# SMA-Q2_replacement_board_v2_2.net
KiCad netlist of a schematic drawn in EAGLE
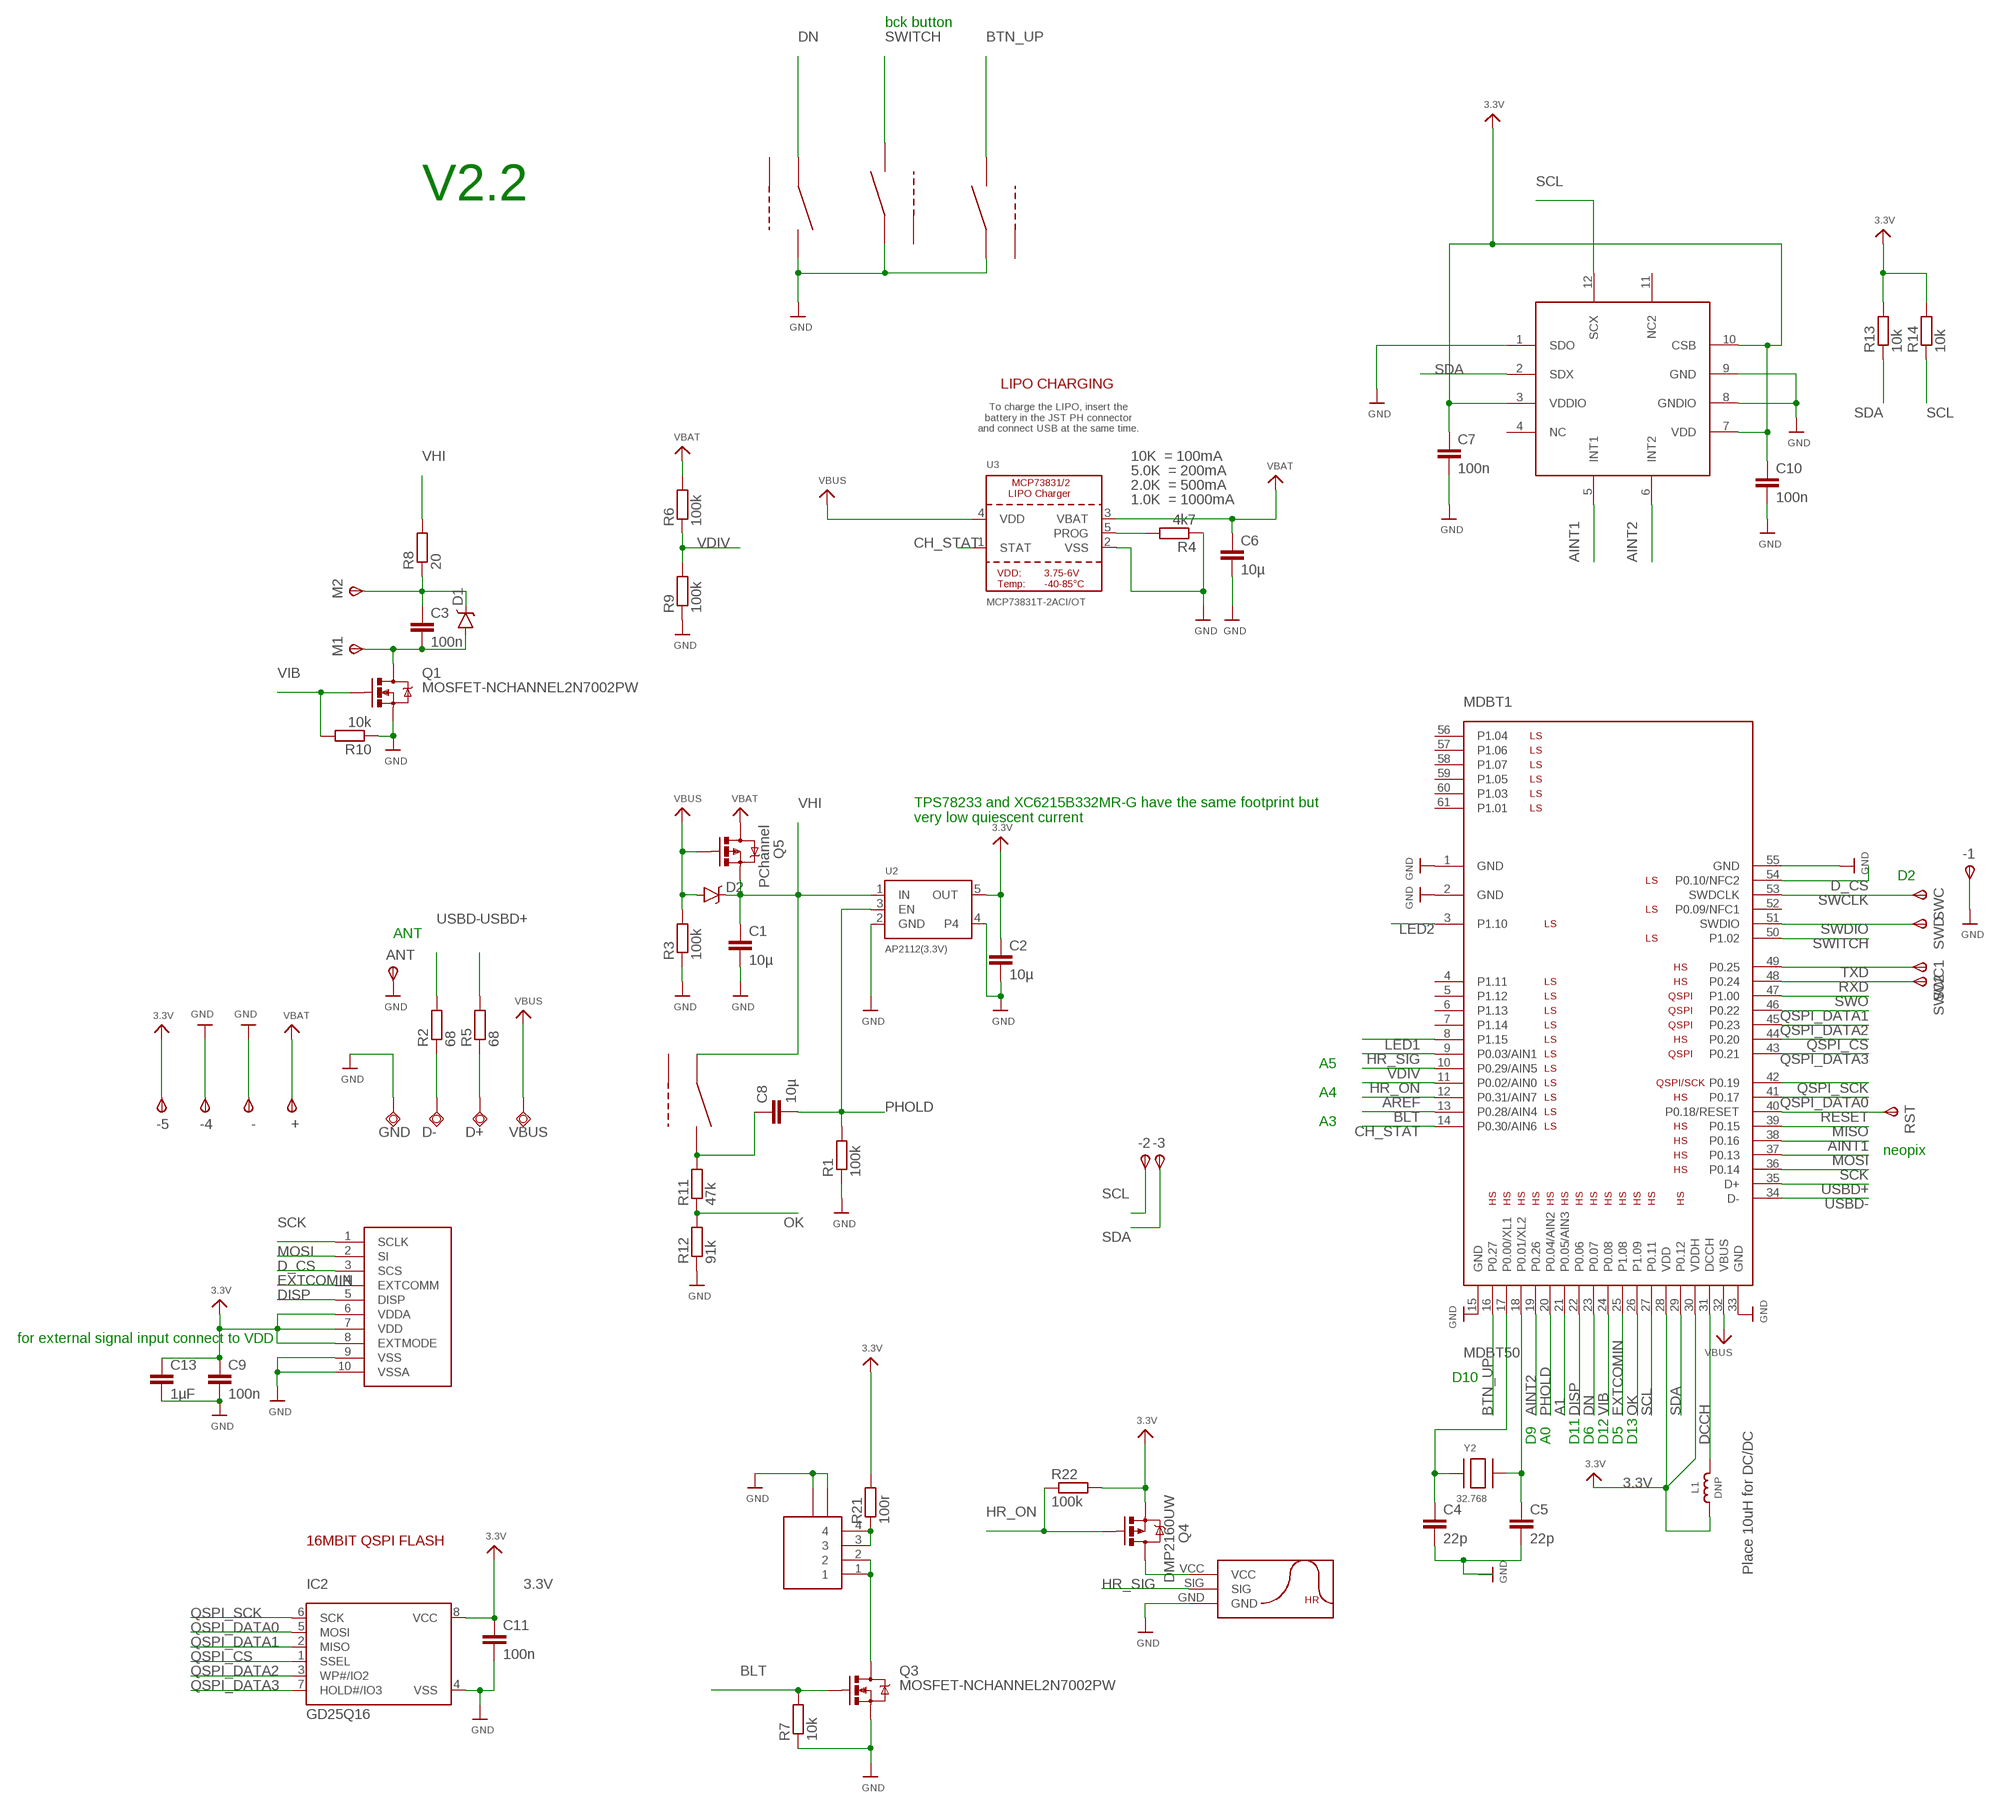
[diagram p0: schematic, sheet 1]

(export (version "E")
  (design (tool "Eeschema 10.0.6"))
  (components
    (comp (ref "+")
      (value "TPSTP09R")
      (footprint "eagle-import:TP09R")
      (libsource (lib "eagle-import") (part "TPSTP09R"))
    )
    (comp (ref "-")
      (value "TPSTP09R")
      (footprint "eagle-import:TP09R")
      (libsource (lib "eagle-import") (part "TPSTP09R"))
    )
    (comp (ref "-1")
      (value "TPSTP09R")
      (footprint "eagle-import:TP09R")
      (libsource (lib "eagle-import") (part "TPSTP09R"))
    )
    (comp (ref "-2")
      (value "TPSTP09R")
      (footprint "eagle-import:TP09R")
      (libsource (lib "eagle-import") (part "TPSTP09R"))
    )
    (comp (ref "-3")
      (value "TPSTP09R")
      (footprint "eagle-import:TP09R")
      (libsource (lib "eagle-import") (part "TPSTP09R"))
    )
    (comp (ref "-4")
      (value "TPSTP09R")
      (footprint "eagle-import:TP09R")
      (libsource (lib "eagle-import") (part "TPSTP09R"))
    )
    (comp (ref "-5")
      (value "TPSTP09R")
      (footprint "eagle-import:TP09R")
      (libsource (lib "eagle-import") (part "TPSTP09R"))
    )
    (comp (ref "ANT")
      (value "TPSTP19SQ")
      (footprint "eagle-import:TP19SQ")
      (libsource (lib "eagle-import") (part "TPSTP19SQ"))
    )
    (comp (ref "C1")
      (value "10µ")
      (footprint "eagle-import:C0603")
      (libsource (lib "eagle-import") (part "C-EUC0603"))
    )
    (comp (ref "C2")
      (value "10µ")
      (footprint "eagle-import:C0603")
      (libsource (lib "eagle-import") (part "C-EUC0603"))
    )
    (comp (ref "C3")
      (value "100n")
      (footprint "eagle-import:C0402")
      (libsource (lib "eagle-import") (part "C-EUC0402"))
    )
    (comp (ref "C4")
      (value "22p")
      (footprint "eagle-import:C0402")
      (libsource (lib "eagle-import") (part "C-EUC0402"))
    )
    (comp (ref "C5")
      (value "22p")
      (footprint "eagle-import:C0402")
      (libsource (lib "eagle-import") (part "C-EUC0402"))
    )
    (comp (ref "C6")
      (value "10µ")
      (footprint "eagle-import:C0603")
      (libsource (lib "eagle-import") (part "C-EUC0603"))
    )
    (comp (ref "C7")
      (value "100n")
      (footprint "eagle-import:C0402")
      (libsource (lib "eagle-import") (part "C-EUC0402"))
    )
    (comp (ref "C8")
      (value "10µ")
      (footprint "eagle-import:C0603")
      (libsource (lib "eagle-import") (part "C-EUC0603"))
    )
    (comp (ref "C9")
      (value "100n")
      (footprint "eagle-import:C0402")
      (libsource (lib "eagle-import") (part "C-EUC0402"))
    )
    (comp (ref "C10")
      (value "100n")
      (footprint "eagle-import:C0402")
      (libsource (lib "eagle-import") (part "C-EUC0402"))
    )
    (comp (ref "C11")
      (value "100n")
      (footprint "eagle-import:C0402")
      (libsource (lib "eagle-import") (part "C-EUC0402"))
    )
    (comp (ref "C13")
      (value "1µF")
      (footprint "eagle-import:C0402")
      (libsource (lib "eagle-import") (part "C-EUC0402"))
    )
    (comp (ref "D+")
      (value "TPSQTP20R")
      (footprint "eagle-import:TP20R")
      (libsource (lib "eagle-import") (part "TPSQTP20R"))
    )
    (comp (ref "D-")
      (value "TPSQTP20R")
      (footprint "eagle-import:TP20R")
      (libsource (lib "eagle-import") (part "TPSQTP20R"))
    )
    (comp (ref "D1")
      (value "BAT20J")
      (footprint "eagle-import:SOD-323")
      (libsource (lib "eagle-import") (part "DIODE-SCHOTTKY-BAT20J"))
    )
    (comp (ref "D2")
      (value "BAT20J")
      (footprint "eagle-import:SOD-323")
      (libsource (lib "eagle-import") (part "DIODE-SCHOTTKY-BAT20J"))
    )
    (comp (ref "DWN")
      (value "LS12T2")
      (footprint "eagle-import:LS12T2")
      (libsource (lib "eagle-import") (part "LS12T2"))
    )
    (comp (ref "DWN1")
      (value "LS12T2")
      (footprint "eagle-import:LS12T2")
      (libsource (lib "eagle-import") (part "LS12T2"))
    )
    (comp (ref "DWN2")
      (value "LS12T2")
      (footprint "eagle-import:LS12T2")
      (libsource (lib "eagle-import") (part "LS12T2"))
    )
    (comp (ref "DWN3")
      (value "LS12T2")
      (footprint "eagle-import:LS12T2")
      (libsource (lib "eagle-import") (part "LS12T2"))
    )
    (comp (ref "GND")
      (value "TPSQTP20R")
      (footprint "eagle-import:TP20R")
      (libsource (lib "eagle-import") (part "TPSQTP20R"))
    )
    (comp (ref "IC2")
      (value "GD25Q16")
      (footprint "eagle-import:USON8")
      (libsource (lib "eagle-import") (part "SPIFLASH_8PINUX"))
    )
    (comp (ref "L1")
      (value "DNP")
      (footprint "eagle-import:_0805MP")
      (libsource (lib "eagle-import") (part "INDUCTOR_0805MP"))
    )
    (comp (ref "M1")
      (value "TPSTP09R")
      (footprint "eagle-import:TP09R")
      (libsource (lib "eagle-import") (part "TPSTP09R"))
    )
    (comp (ref "M2")
      (value "TPSTP09R")
      (footprint "eagle-import:TP09R")
      (libsource (lib "eagle-import") (part "TPSTP09R"))
    )
    (comp (ref "MDBT1")
      (value "MDBT50")
      (footprint "eagle-import:MDBT50")
      (libsource (lib "eagle-import") (part "MDBT50"))
    )
    (comp (ref "Q1")
      (value "MOSFET-NCHANNEL2N7002PW")
      (footprint "eagle-import:SOT323")
      (libsource (lib "eagle-import") (part "MOSFET-NCHANNEL2N7002PW"))
    )
    (comp (ref "Q3")
      (value "MOSFET-NCHANNEL2N7002PW")
      (footprint "eagle-import:SOT323")
      (libsource (lib "eagle-import") (part "MOSFET-NCHANNEL2N7002PW"))
    )
    (comp (ref "Q4")
      (value "DMP2160UW")
      (footprint "eagle-import:SOT323")
      (libsource (lib "eagle-import") (part "MOSFET-P-CHANNEL-DMP2160UW"))
    )
    (comp (ref "Q5")
      (value "PChannel")
      (footprint "eagle-import:SOT323")
      (libsource (lib "eagle-import") (part "MOSFET-P-CHANNEL-DMP2160UW"))
    )
    (comp (ref "R1")
      (value "100k")
      (footprint "eagle-import:R0402")
      (libsource (lib "eagle-import") (part "R-EU_R0402"))
    )
    (comp (ref "R2")
      (value "68")
      (footprint "eagle-import:R0402")
      (libsource (lib "eagle-import") (part "R-EU_R0402"))
    )
    (comp (ref "R3")
      (value "100k")
      (footprint "eagle-import:R0402")
      (libsource (lib "eagle-import") (part "R-EU_R0402"))
    )
    (comp (ref "R4")
      (value "4k7")
      (footprint "eagle-import:R0402")
      (libsource (lib "eagle-import") (part "R-EU_R0402"))
    )
    (comp (ref "R5")
      (value "68")
      (footprint "eagle-import:R0402")
      (libsource (lib "eagle-import") (part "R-EU_R0402"))
    )
    (comp (ref "R6")
      (value "100k")
      (footprint "eagle-import:R0402")
      (libsource (lib "eagle-import") (part "R-EU_R0402"))
    )
    (comp (ref "R7")
      (value "10k")
      (footprint "eagle-import:R0402")
      (libsource (lib "eagle-import") (part "R-EU_R0402"))
    )
    (comp (ref "R8")
      (value "20")
      (footprint "eagle-import:R0402")
      (libsource (lib "eagle-import") (part "R-EU_R0402"))
    )
    (comp (ref "R9")
      (value "100k")
      (footprint "eagle-import:R0402")
      (libsource (lib "eagle-import") (part "R-EU_R0402"))
    )
    (comp (ref "R10")
      (value "10k")
      (footprint "eagle-import:R0402")
      (libsource (lib "eagle-import") (part "R-EU_R0402"))
    )
    (comp (ref "R11")
      (value "47k")
      (footprint "eagle-import:R0402")
      (libsource (lib "eagle-import") (part "R-EU_R0402"))
    )
    (comp (ref "R12")
      (value "91k")
      (footprint "eagle-import:R0402")
      (libsource (lib "eagle-import") (part "R-EU_R0402"))
    )
    (comp (ref "R13")
      (value "10k")
      (footprint "eagle-import:R0402")
      (libsource (lib "eagle-import") (part "R-EU_R0402"))
    )
    (comp (ref "R14")
      (value "10k")
      (footprint "eagle-import:R0402")
      (libsource (lib "eagle-import") (part "R-EU_R0402"))
    )
    (comp (ref "R21")
      (value "100r")
      (footprint "eagle-import:R0402")
      (libsource (lib "eagle-import") (part "R-EU_R0402"))
    )
    (comp (ref "R22")
      (value "100k")
      (footprint "eagle-import:R0402")
      (libsource (lib "eagle-import") (part "R-EU_R0402"))
    )
    (comp (ref "RST")
      (value "TPSTP09R")
      (footprint "eagle-import:TP09R")
      (libsource (lib "eagle-import") (part "TPSTP09R"))
    )
    (comp (ref "SWC")
      (value "TPSTP09R")
      (footprint "eagle-import:TP09R")
      (libsource (lib "eagle-import") (part "TPSTP09R"))
    )
    (comp (ref "SWC1")
      (value "TPSTP09R")
      (footprint "eagle-import:TP09R")
      (libsource (lib "eagle-import") (part "TPSTP09R"))
    )
    (comp (ref "SWC2")
      (value "TPSTP09R")
      (footprint "eagle-import:TP09R")
      (libsource (lib "eagle-import") (part "TPSTP09R"))
    )
    (comp (ref "SWD")
      (value "TPSTP09R")
      (footprint "eagle-import:TP09R")
      (libsource (lib "eagle-import") (part "TPSTP09R"))
    )
    (comp (ref "U$2")
      (value "SHARP_MEM_DISP")
      (footprint "eagle-import:Y5BW")
      (libsource (lib "eagle-import") (part "SHARP_MEM_DISP"))
    )
    (comp (ref "U$6")
      (value "Y5B-4PIN")
      (footprint "eagle-import:Y5B-4PIN")
      (libsource (lib "eagle-import") (part "Y5B-4PIN"))
    )
    (comp (ref "U$7")
      (value "BMA400")
      (footprint "eagle-import:BMA400")
      (libsource (lib "eagle-import") (part "BMA400"))
    )
    (comp (ref "U$45")
      (value "HR_PADS")
      (footprint "eagle-import:HR_PADS")
      (libsource (lib "eagle-import") (part "HR_PADS"))
    )
    (comp (ref "U2")
      (value "AP2112(3.3V)")
      (footprint "eagle-import:SOT23-5")
      (libsource (lib "eagle-import") (part "VREG_SOT23-5"))
    )
    (comp (ref "U3")
      (value "MCP73831T-2ACI/OT")
      (footprint "eagle-import:SOT23-5")
      (libsource (lib "eagle-import") (part "MCP73831/2"))
    )
    (comp (ref "VBUS")
      (value "TPSQTP20R")
      (footprint "eagle-import:TP20R")
      (libsource (lib "eagle-import") (part "TPSQTP20R"))
    )
    (comp (ref "Y2")
      (value "32.768")
      (footprint "eagle-import:XTAL3215")
      (libsource (lib "eagle-import") (part "XTAL-3.2X1.5"))
    )
  )
  (nets
    (net (code "1") (name "/A1") (class "Default")
      (node (ref "MDBT1") (pin "21") (pinfunction "P0.05/AIN3_21") (pintype "bidirectional"))
    )
    (net (code "2") (name "/AINT1") (class "Default")
      (node (ref "MDBT1") (pin "38") (pinfunction "P0.16_38") (pintype "bidirectional"))
      (node (ref "U$7") (pin "5") (pinfunction "INT1_5") (pintype "bidirectional"))
    )
    (net (code "3") (name "/AINT2") (class "Default")
      (node (ref "MDBT1") (pin "19") (pinfunction "P0.26_19") (pintype "bidirectional"))
      (node (ref "U$7") (pin "6") (pinfunction "INT2_6") (pintype "bidirectional"))
    )
    (net (code "4") (name "/AREF") (class "Default")
      (node (ref "MDBT1") (pin "12") (pinfunction "P0.31/AIN7_12") (pintype "bidirectional"))
    )
    (net (code "5") (name "/BLT") (class "Default")
      (node (ref "MDBT1") (pin "13") (pinfunction "P0.28/AIN4_13") (pintype "bidirectional"))
      (node (ref "Q3") (pin "1") (pinfunction "G_1") (pintype "passive"))
      (node (ref "R7") (pin "2") (pinfunction "2_2") (pintype "passive"))
    )
    (net (code "6") (name "/BTN_UP") (class "Default")
      (node (ref "DWN2") (pin "1") (pinfunction "1_1") (pintype "bidirectional"))
      (node (ref "MDBT1") (pin "16") (pinfunction "P0.27_16") (pintype "bidirectional"))
    )
    (net (code "7") (name "/CH_STAT") (class "Default")
      (node (ref "MDBT1") (pin "14") (pinfunction "P0.30/AIN6_14") (pintype "bidirectional"))
      (node (ref "U3") (pin "1") (pinfunction "STAT_1") (pintype "output"))
    )
    (net (code "8") (name "/DCCH") (class "Default")
      (node (ref "L1") (pin "2") (pinfunction "2_2") (pintype "passive"))
      (node (ref "MDBT1") (pin "31") (pinfunction "DCCH_31") (pintype "bidirectional"))
    )
    (net (code "9") (name "/DISP") (class "Default")
      (node (ref "MDBT1") (pin "22") (pinfunction "P0.06_22") (pintype "bidirectional"))
      (node (ref "U$2") (pin "5") (pinfunction "DISP_5") (pintype "bidirectional"))
    )
    (net (code "10") (name "/DN") (class "Default")
      (node (ref "DWN") (pin "2") (pinfunction "2_2") (pintype "bidirectional"))
      (node (ref "MDBT1") (pin "23") (pinfunction "P0.07_23") (pintype "bidirectional"))
    )
    (net (code "11") (name "/D_CS") (class "Default")
      (node (ref "MDBT1") (pin "54") (pinfunction "P0.10/NFC2_54") (pintype "bidirectional"))
      (node (ref "U$2") (pin "3") (pinfunction "SCS_3") (pintype "bidirectional"))
    )
    (net (code "12") (name "/EXTCOMIN") (class "Default")
      (node (ref "MDBT1") (pin "25") (pinfunction "P1.08_25") (pintype "bidirectional"))
      (node (ref "U$2") (pin "4") (pinfunction "EXTCOMM_4") (pintype "bidirectional"))
    )
    (net (code "13") (name "/HR_ON") (class "Default")
      (node (ref "MDBT1") (pin "11") (pinfunction "P0.02/AIN0_11") (pintype "bidirectional"))
      (node (ref "Q4") (pin "1") (pinfunction "G_1") (pintype "passive"))
      (node (ref "R22") (pin "1") (pinfunction "1_1") (pintype "passive"))
    )
    (net (code "14") (name "/HR_SIG") (class "Default")
      (node (ref "MDBT1") (pin "9") (pinfunction "P0.03/AIN1_9") (pintype "bidirectional"))
      (node (ref "U$45") (pin "SIG") (pinfunction "SIG_SIG") (pintype "bidirectional"))
    )
    (net (code "15") (name "/LED1") (class "Default")
      (node (ref "MDBT1") (pin "8") (pinfunction "P1.15_8") (pintype "bidirectional"))
    )
    (net (code "16") (name "/LED2") (class "Default")
      (node (ref "MDBT1") (pin "3") (pinfunction "P1.10_3") (pintype "bidirectional"))
    )
    (net (code "17") (name "/MISO") (class "Default")
      (node (ref "MDBT1") (pin "39") (pinfunction "P0.15_39") (pintype "bidirectional"))
    )
    (net (code "18") (name "/MOSI") (class "Default")
      (node (ref "MDBT1") (pin "37") (pinfunction "P0.13_37") (pintype "bidirectional"))
      (node (ref "U$2") (pin "2") (pinfunction "SI_2") (pintype "bidirectional"))
    )
    (net (code "19") (name "/OK") (class "Default")
      (node (ref "MDBT1") (pin "26") (pinfunction "P1.09_26") (pintype "bidirectional"))
      (node (ref "R11") (pin "1") (pinfunction "1_1") (pintype "passive"))
      (node (ref "R12") (pin "2") (pinfunction "2_2") (pintype "passive"))
    )
    (net (code "20") (name "/PHOLD") (class "Default")
      (node (ref "C8") (pin "2") (pinfunction "2_2") (pintype "passive"))
      (node (ref "MDBT1") (pin "20") (pinfunction "P0.04/AIN2_20") (pintype "bidirectional"))
      (node (ref "R1") (pin "2") (pinfunction "2_2") (pintype "passive"))
      (node (ref "U2") (pin "3") (pinfunction "EN_3") (pintype "input"))
    )
    (net (code "21") (name "/QSPI_CS") (class "Default")
      (node (ref "IC2") (pin "1") (pinfunction "SSEL_1") (pintype "bidirectional"))
      (node (ref "MDBT1") (pin "44") (pinfunction "P0.20_44") (pintype "bidirectional"))
    )
    (net (code "22") (name "/QSPI_DATA0") (class "Default")
      (node (ref "IC2") (pin "5") (pinfunction "MOSI_5") (pintype "bidirectional"))
      (node (ref "MDBT1") (pin "41") (pinfunction "P0.17_41") (pintype "bidirectional"))
    )
    (net (code "23") (name "/QSPI_DATA1") (class "Default")
      (node (ref "IC2") (pin "2") (pinfunction "MISO_2") (pintype "bidirectional"))
      (node (ref "MDBT1") (pin "46") (pinfunction "P0.22_46") (pintype "bidirectional"))
    )
    (net (code "24") (name "/QSPI_DATA2") (class "Default")
      (node (ref "IC2") (pin "3") (pinfunction "WP#/IO2_3") (pintype "bidirectional"))
      (node (ref "MDBT1") (pin "45") (pinfunction "P0.23_45") (pintype "bidirectional"))
    )
    (net (code "25") (name "/QSPI_DATA3") (class "Default")
      (node (ref "IC2") (pin "7") (pinfunction "HOLD#/IO3_7") (pintype "bidirectional"))
      (node (ref "MDBT1") (pin "43") (pinfunction "P0.21_43") (pintype "bidirectional"))
    )
    (net (code "26") (name "/QSPI_SCK") (class "Default")
      (node (ref "IC2") (pin "6") (pinfunction "SCK_6") (pintype "bidirectional"))
      (node (ref "MDBT1") (pin "42") (pinfunction "P0.19_42") (pintype "bidirectional"))
    )
    (net (code "27") (name "/RESET") (class "Default")
      (node (ref "MDBT1") (pin "40") (pinfunction "P0.18/RESET_40") (pintype "bidirectional"))
      (node (ref "RST") (pin "TP") (pinfunction "PP_TP") (pintype "input"))
    )
    (net (code "28") (name "/RXD") (class "Default")
      (node (ref "MDBT1") (pin "48") (pinfunction "P0.24_48") (pintype "bidirectional"))
      (node (ref "SWC2") (pin "TP") (pinfunction "PP_TP") (pintype "input"))
    )
    (net (code "29") (name "/SCK") (class "Default")
      (node (ref "MDBT1") (pin "36") (pinfunction "P0.14_36") (pintype "bidirectional"))
      (node (ref "U$2") (pin "1") (pinfunction "SCLK_1") (pintype "bidirectional"))
    )
    (net (code "30") (name "/SCL") (class "Default")
      (node (ref "-2") (pin "TP") (pinfunction "PP_TP") (pintype "input"))
      (node (ref "MDBT1") (pin "27") (pinfunction "P0.11_27") (pintype "bidirectional"))
      (node (ref "R14") (pin "1") (pinfunction "1_1") (pintype "passive"))
      (node (ref "U$7") (pin "12") (pinfunction "SCX_12") (pintype "bidirectional"))
    )
    (net (code "31") (name "/SDA") (class "Default")
      (node (ref "-3") (pin "TP") (pinfunction "PP_TP") (pintype "input"))
      (node (ref "MDBT1") (pin "29") (pinfunction "P0.12_29") (pintype "bidirectional"))
      (node (ref "R13") (pin "1") (pinfunction "1_1") (pintype "passive"))
      (node (ref "U$7") (pin "2") (pinfunction "SDX_2") (pintype "bidirectional"))
    )
    (net (code "32") (name "/SWCLK") (class "Default")
      (node (ref "MDBT1") (pin "53") (pinfunction "SWDCLK_53") (pintype "bidirectional"))
      (node (ref "SWC") (pin "TP") (pinfunction "PP_TP") (pintype "input"))
    )
    (net (code "33") (name "/SWDIO") (class "Default")
      (node (ref "MDBT1") (pin "51") (pinfunction "SWDIO_51") (pintype "bidirectional"))
      (node (ref "SWD") (pin "TP") (pinfunction "PP_TP") (pintype "input"))
    )
    (net (code "34") (name "/SWITCH") (class "Default")
      (node (ref "DWN1") (pin "1") (pinfunction "1_1") (pintype "bidirectional"))
      (node (ref "MDBT1") (pin "50") (pinfunction "P1.02_50") (pintype "bidirectional"))
    )
    (net (code "35") (name "/SWO") (class "Default")
      (node (ref "MDBT1") (pin "47") (pinfunction "P1.00_47") (pintype "bidirectional"))
    )
    (net (code "36") (name "/TXD") (class "Default")
      (node (ref "MDBT1") (pin "49") (pinfunction "P0.25_49") (pintype "bidirectional"))
      (node (ref "SWC1") (pin "TP") (pinfunction "PP_TP") (pintype "input"))
    )
    (net (code "37") (name "/USBD+") (class "Default")
      (node (ref "MDBT1") (pin "35") (pinfunction "D+_35") (pintype "bidirectional"))
      (node (ref "R5") (pin "2") (pinfunction "2_2") (pintype "passive"))
    )
    (net (code "38") (name "/USBD-") (class "Default")
      (node (ref "MDBT1") (pin "34") (pinfunction "D-_34") (pintype "bidirectional"))
      (node (ref "R2") (pin "2") (pinfunction "2_2") (pintype "passive"))
    )
    (net (code "39") (name "/VDIV") (class "Default")
      (node (ref "MDBT1") (pin "10") (pinfunction "P0.29/AIN5_10") (pintype "bidirectional"))
      (node (ref "R6") (pin "1") (pinfunction "1_1") (pintype "passive"))
      (node (ref "R9") (pin "2") (pinfunction "2_2") (pintype "passive"))
    )
    (net (code "40") (name "/VHI") (class "Default")
      (node (ref "C1") (pin "1") (pinfunction "1_1") (pintype "passive"))
      (node (ref "D2") (pin "C") (pinfunction "C_C") (pintype "passive"))
      (node (ref "DWN3") (pin "2") (pinfunction "2_2") (pintype "bidirectional"))
      (node (ref "Q5") (pin "2") (pinfunction "S_2") (pintype "passive"))
      (node (ref "R8") (pin "2") (pinfunction "2_2") (pintype "passive"))
      (node (ref "U2") (pin "1") (pinfunction "IN_1") (pintype "power_in"))
    )
    (net (code "41") (name "/VIB") (class "Default")
      (node (ref "MDBT1") (pin "24") (pinfunction "P0.08_24") (pintype "bidirectional"))
      (node (ref "Q1") (pin "1") (pinfunction "G_1") (pintype "passive"))
      (node (ref "R10") (pin "2") (pinfunction "2_2") (pintype "passive"))
    )
    (net (code "42") (name "3.3V") (class "Default")
      (node (ref "-5") (pin "TP") (pinfunction "PP_TP") (pintype "input"))
      (node (ref "C10") (pin "1") (pinfunction "1_1") (pintype "passive"))
      (node (ref "C11") (pin "1") (pinfunction "1_1") (pintype "passive"))
      (node (ref "C13") (pin "1") (pinfunction "1_1") (pintype "passive"))
      (node (ref "C2") (pin "1") (pinfunction "1_1") (pintype "passive"))
      (node (ref "C7") (pin "1") (pinfunction "1_1") (pintype "passive"))
      (node (ref "C9") (pin "1") (pinfunction "1_1") (pintype "passive"))
      (node (ref "IC2") (pin "8") (pinfunction "VCC_8") (pintype "bidirectional"))
      (node (ref "L1") (pin "1") (pinfunction "1_1") (pintype "passive"))
      (node (ref "MDBT1") (pin "28") (pinfunction "VDD_28") (pintype "bidirectional"))
      (node (ref "MDBT1") (pin "30") (pinfunction "VDDH_30") (pintype "bidirectional"))
      (node (ref "Q4") (pin "2") (pinfunction "S_2") (pintype "passive"))
      (node (ref "R13") (pin "2") (pinfunction "2_2") (pintype "passive"))
      (node (ref "R14") (pin "2") (pinfunction "2_2") (pintype "passive"))
      (node (ref "R21") (pin "2") (pinfunction "2_2") (pintype "passive"))
      (node (ref "R22") (pin "2") (pinfunction "2_2") (pintype "passive"))
      (node (ref "U$2") (pin "6") (pinfunction "VDDA_6") (pintype "bidirectional"))
      (node (ref "U$2") (pin "7") (pinfunction "VDD_7") (pintype "bidirectional"))
      (node (ref "U$2") (pin "8") (pinfunction "EXTMODE_8") (pintype "bidirectional"))
      (node (ref "U$7") (pin "10") (pinfunction "CSB_10") (pintype "bidirectional"))
      (node (ref "U$7") (pin "3") (pinfunction "VDDIO_3") (pintype "bidirectional"))
      (node (ref "U$7") (pin "7") (pinfunction "VDD_7") (pintype "bidirectional"))
      (node (ref "U2") (pin "5") (pinfunction "OUT_5") (pintype "power_in"))
    )
    (net (code "43") (name "GND") (class "Default")
      (node (ref "-") (pin "TP") (pinfunction "PP_TP") (pintype "input"))
      (node (ref "-1") (pin "TP") (pinfunction "PP_TP") (pintype "input"))
      (node (ref "-4") (pin "TP") (pinfunction "PP_TP") (pintype "input"))
      (node (ref "ANT") (pin "TP") (pinfunction "PP_TP") (pintype "input"))
      (node (ref "C1") (pin "2") (pinfunction "2_2") (pintype "passive"))
      (node (ref "C10") (pin "2") (pinfunction "2_2") (pintype "passive"))
      (node (ref "C11") (pin "2") (pinfunction "2_2") (pintype "passive"))
      (node (ref "C13") (pin "2") (pinfunction "2_2") (pintype "passive"))
      (node (ref "C2") (pin "2") (pinfunction "2_2") (pintype "passive"))
      (node (ref "C4") (pin "2") (pinfunction "2_2") (pintype "passive"))
      (node (ref "C5") (pin "2") (pinfunction "2_2") (pintype "passive"))
      (node (ref "C6") (pin "2") (pinfunction "2_2") (pintype "passive"))
      (node (ref "C7") (pin "2") (pinfunction "2_2") (pintype "passive"))
      (node (ref "C9") (pin "2") (pinfunction "2_2") (pintype "passive"))
      (node (ref "DWN") (pin "1") (pinfunction "1_1") (pintype "bidirectional"))
      (node (ref "DWN1") (pin "2") (pinfunction "2_2") (pintype "bidirectional"))
      (node (ref "DWN2") (pin "2") (pinfunction "2_2") (pintype "bidirectional"))
      (node (ref "GND") (pin "TP") (pinfunction "TP_TP") (pintype "input"))
      (node (ref "IC2") (pin "4") (pinfunction "VSS_4") (pintype "bidirectional"))
      (node (ref "MDBT1") (pin "1") (pinfunction "GND_1") (pintype "bidirectional"))
      (node (ref "MDBT1") (pin "15") (pinfunction "GND_15") (pintype "bidirectional"))
      (node (ref "MDBT1") (pin "2") (pinfunction "GND_2") (pintype "bidirectional"))
      (node (ref "MDBT1") (pin "33") (pinfunction "GND_33") (pintype "bidirectional"))
      (node (ref "MDBT1") (pin "55") (pinfunction "GND_55") (pintype "bidirectional"))
      (node (ref "Q1") (pin "2") (pinfunction "S_2") (pintype "passive"))
      (node (ref "Q3") (pin "2") (pinfunction "S_2") (pintype "passive"))
      (node (ref "R1") (pin "1") (pinfunction "1_1") (pintype "passive"))
      (node (ref "R10") (pin "1") (pinfunction "1_1") (pintype "passive"))
      (node (ref "R12") (pin "1") (pinfunction "1_1") (pintype "passive"))
      (node (ref "R3") (pin "1") (pinfunction "1_1") (pintype "passive"))
      (node (ref "R4") (pin "1") (pinfunction "1_1") (pintype "passive"))
      (node (ref "R7") (pin "1") (pinfunction "1_1") (pintype "passive"))
      (node (ref "R9") (pin "1") (pinfunction "1_1") (pintype "passive"))
      (node (ref "U$2") (pin "10") (pinfunction "VSSA_10") (pintype "bidirectional"))
      (node (ref "U$2") (pin "9") (pinfunction "VSS_9") (pintype "bidirectional"))
      (node (ref "U$45") (pin "GND") (pinfunction "GND_GND") (pintype "bidirectional"))
      (node (ref "U$6") (pin "H1") (pinfunction "P$5_H1") (pintype "bidirectional"))
      (node (ref "U$6") (pin "H2") (pinfunction "P$6_H2") (pintype "bidirectional"))
      (node (ref "U$7") (pin "1") (pinfunction "SDO_1") (pintype "bidirectional"))
      (node (ref "U$7") (pin "8") (pinfunction "GNDIO_8") (pintype "bidirectional"))
      (node (ref "U$7") (pin "9") (pinfunction "GND_9") (pintype "bidirectional"))
      (node (ref "U2") (pin "2") (pinfunction "GND_2") (pintype "power_in"))
      (node (ref "U2") (pin "4") (pinfunction "P4_4") (pintype "bidirectional"))
      (node (ref "U3") (pin "2") (pinfunction "VSS_2") (pintype "power_in"))
    )
    (net (code "44") (name "Net-(C8-Pad1)") (class "Default")
      (node (ref "C8") (pin "1") (pinfunction "1_1") (pintype "passive"))
      (node (ref "DWN3") (pin "1") (pinfunction "1_1") (pintype "bidirectional"))
      (node (ref "R11") (pin "2") (pinfunction "2_2") (pintype "passive"))
    )
    (net (code "45") (name "Net-(D+-PadTP)") (class "Default")
      (node (ref "D+") (pin "TP") (pinfunction "TP_TP") (pintype "input"))
      (node (ref "R5") (pin "1") (pinfunction "1_1") (pintype "passive"))
    )
    (net (code "46") (name "Net-(D--PadTP)") (class "Default")
      (node (ref "D-") (pin "TP") (pinfunction "TP_TP") (pintype "input"))
      (node (ref "R2") (pin "1") (pinfunction "1_1") (pintype "passive"))
    )
    (net (code "47") (name "Net-(M1-PP)") (class "Default")
      (node (ref "C3") (pin "2") (pinfunction "2_2") (pintype "passive"))
      (node (ref "D1") (pin "A") (pinfunction "A_A") (pintype "passive"))
      (node (ref "M1") (pin "TP") (pinfunction "PP_TP") (pintype "input"))
      (node (ref "Q1") (pin "3") (pinfunction "D_3") (pintype "passive"))
    )
    (net (code "48") (name "Net-(M2-PP)") (class "Default")
      (node (ref "C3") (pin "1") (pinfunction "1_1") (pintype "passive"))
      (node (ref "D1") (pin "C") (pinfunction "C_C") (pintype "passive"))
      (node (ref "M2") (pin "TP") (pinfunction "PP_TP") (pintype "input"))
      (node (ref "R8") (pin "1") (pinfunction "1_1") (pintype "passive"))
    )
    (net (code "49") (name "Net-(MDBT1-P0.00{slash}XL1)") (class "Default")
      (node (ref "C4") (pin "1") (pinfunction "1_1") (pintype "passive"))
      (node (ref "MDBT1") (pin "17") (pinfunction "P0.00/XL1_17") (pintype "bidirectional"))
      (node (ref "Y2") (pin "P$1") (pinfunction "P$1_P$1") (pintype "bidirectional"))
    )
    (net (code "50") (name "Net-(MDBT1-P0.01{slash}XL2)") (class "Default")
      (node (ref "C5") (pin "1") (pinfunction "1_1") (pintype "passive"))
      (node (ref "MDBT1") (pin "18") (pinfunction "P0.01/XL2_18") (pintype "bidirectional"))
      (node (ref "Y2") (pin "P$2") (pinfunction "P$2_P$2") (pintype "bidirectional"))
    )
    (net (code "51") (name "Net-(Q3-D)") (class "Default")
      (node (ref "Q3") (pin "3") (pinfunction "D_3") (pintype "passive"))
      (node (ref "U$6") (pin "1") (pinfunction "1_1") (pintype "bidirectional"))
      (node (ref "U$6") (pin "2") (pinfunction "2_2") (pintype "bidirectional"))
    )
    (net (code "52") (name "Net-(Q4-D)") (class "Default")
      (node (ref "Q4") (pin "3") (pinfunction "D_3") (pintype "passive"))
      (node (ref "U$45") (pin "VCC") (pinfunction "VCC_VCC") (pintype "bidirectional"))
    )
    (net (code "53") (name "Net-(R21-Pad1)") (class "Default")
      (node (ref "R21") (pin "1") (pinfunction "1_1") (pintype "passive"))
      (node (ref "U$6") (pin "3") (pinfunction "3_3") (pintype "bidirectional"))
      (node (ref "U$6") (pin "4") (pinfunction "4_4") (pintype "bidirectional"))
    )
    (net (code "54") (name "Net-(U3-PROG)") (class "Default")
      (node (ref "R4") (pin "2") (pinfunction "2_2") (pintype "passive"))
      (node (ref "U3") (pin "5") (pinfunction "PROG_5") (pintype "input"))
    )
    (net (code "55") (name "VBAT") (class "Default")
      (node (ref "+") (pin "TP") (pinfunction "PP_TP") (pintype "input"))
      (node (ref "C6") (pin "1") (pinfunction "1_1") (pintype "passive"))
      (node (ref "Q5") (pin "3") (pinfunction "D_3") (pintype "passive"))
      (node (ref "R6") (pin "2") (pinfunction "2_2") (pintype "passive"))
      (node (ref "U3") (pin "3") (pinfunction "VBAT_3") (pintype "power_in"))
    )
    (net (code "56") (name "VBUS") (class "Default")
      (node (ref "D2") (pin "A") (pinfunction "A_A") (pintype "passive"))
      (node (ref "MDBT1") (pin "32") (pinfunction "VBUS_32") (pintype "bidirectional"))
      (node (ref "Q5") (pin "1") (pinfunction "G_1") (pintype "passive"))
      (node (ref "R3") (pin "2") (pinfunction "2_2") (pintype "passive"))
      (node (ref "U3") (pin "4") (pinfunction "VDD_4") (pintype "power_in"))
      (node (ref "VBUS") (pin "TP") (pinfunction "TP_TP") (pintype "input"))
    )
    (net (code "57") (name "unconnected-(DWN-FRM-PadFRAME)") (class "Default")
      (node (ref "DWN") (pin "FRAME") (pinfunction "FRM_FRAME") (pintype "bidirectional"))
    )
    (net (code "58") (name "unconnected-(DWN1-FRM-PadFRAME)") (class "Default")
      (node (ref "DWN1") (pin "FRAME") (pinfunction "FRM_FRAME") (pintype "bidirectional"))
    )
    (net (code "59") (name "unconnected-(DWN2-FRM-PadFRAME)") (class "Default")
      (node (ref "DWN2") (pin "FRAME") (pinfunction "FRM_FRAME") (pintype "bidirectional"))
    )
    (net (code "60") (name "unconnected-(DWN3-FRM-PadFRAME)") (class "Default")
      (node (ref "DWN3") (pin "FRAME") (pinfunction "FRM_FRAME") (pintype "bidirectional"))
    )
    (net (code "61") (name "unconnected-(MDBT1-P0.09{slash}NFC1-Pad52)") (class "Default")
      (node (ref "MDBT1") (pin "52") (pinfunction "P0.09/NFC1_52") (pintype "bidirectional"))
    )
    (net (code "62") (name "unconnected-(MDBT1-P1.01-Pad61)") (class "Default")
      (node (ref "MDBT1") (pin "61") (pinfunction "P1.01_61") (pintype "bidirectional"))
    )
    (net (code "63") (name "unconnected-(MDBT1-P1.03-Pad60)") (class "Default")
      (node (ref "MDBT1") (pin "60") (pinfunction "P1.03_60") (pintype "bidirectional"))
    )
    (net (code "64") (name "unconnected-(MDBT1-P1.04-Pad56)") (class "Default")
      (node (ref "MDBT1") (pin "56") (pinfunction "P1.04_56") (pintype "bidirectional"))
    )
    (net (code "65") (name "unconnected-(MDBT1-P1.05-Pad59)") (class "Default")
      (node (ref "MDBT1") (pin "59") (pinfunction "P1.05_59") (pintype "bidirectional"))
    )
    (net (code "66") (name "unconnected-(MDBT1-P1.06-Pad57)") (class "Default")
      (node (ref "MDBT1") (pin "57") (pinfunction "P1.06_57") (pintype "bidirectional"))
    )
    (net (code "67") (name "unconnected-(MDBT1-P1.07-Pad58)") (class "Default")
      (node (ref "MDBT1") (pin "58") (pinfunction "P1.07_58") (pintype "bidirectional"))
    )
    (net (code "68") (name "unconnected-(MDBT1-P1.11-Pad4)") (class "Default")
      (node (ref "MDBT1") (pin "4") (pinfunction "P1.11_4") (pintype "bidirectional"))
    )
    (net (code "69") (name "unconnected-(MDBT1-P1.12-Pad5)") (class "Default")
      (node (ref "MDBT1") (pin "5") (pinfunction "P1.12_5") (pintype "bidirectional"))
    )
    (net (code "70") (name "unconnected-(MDBT1-P1.13-Pad6)") (class "Default")
      (node (ref "MDBT1") (pin "6") (pinfunction "P1.13_6") (pintype "bidirectional"))
    )
    (net (code "71") (name "unconnected-(MDBT1-P1.14-Pad7)") (class "Default")
      (node (ref "MDBT1") (pin "7") (pinfunction "P1.14_7") (pintype "bidirectional"))
    )
    (net (code "72") (name "unconnected-(U$7-NC-Pad4)") (class "Default")
      (node (ref "U$7") (pin "4") (pinfunction "NC_4") (pintype "bidirectional"))
    )
    (net (code "73") (name "unconnected-(U$7-NC2-Pad11)") (class "Default")
      (node (ref "U$7") (pin "11") (pinfunction "NC2_11") (pintype "bidirectional"))
    )
  )
)
